# slush_alt_board_rev_c.net
KiCad netlist of a schematic drawn in EAGLE
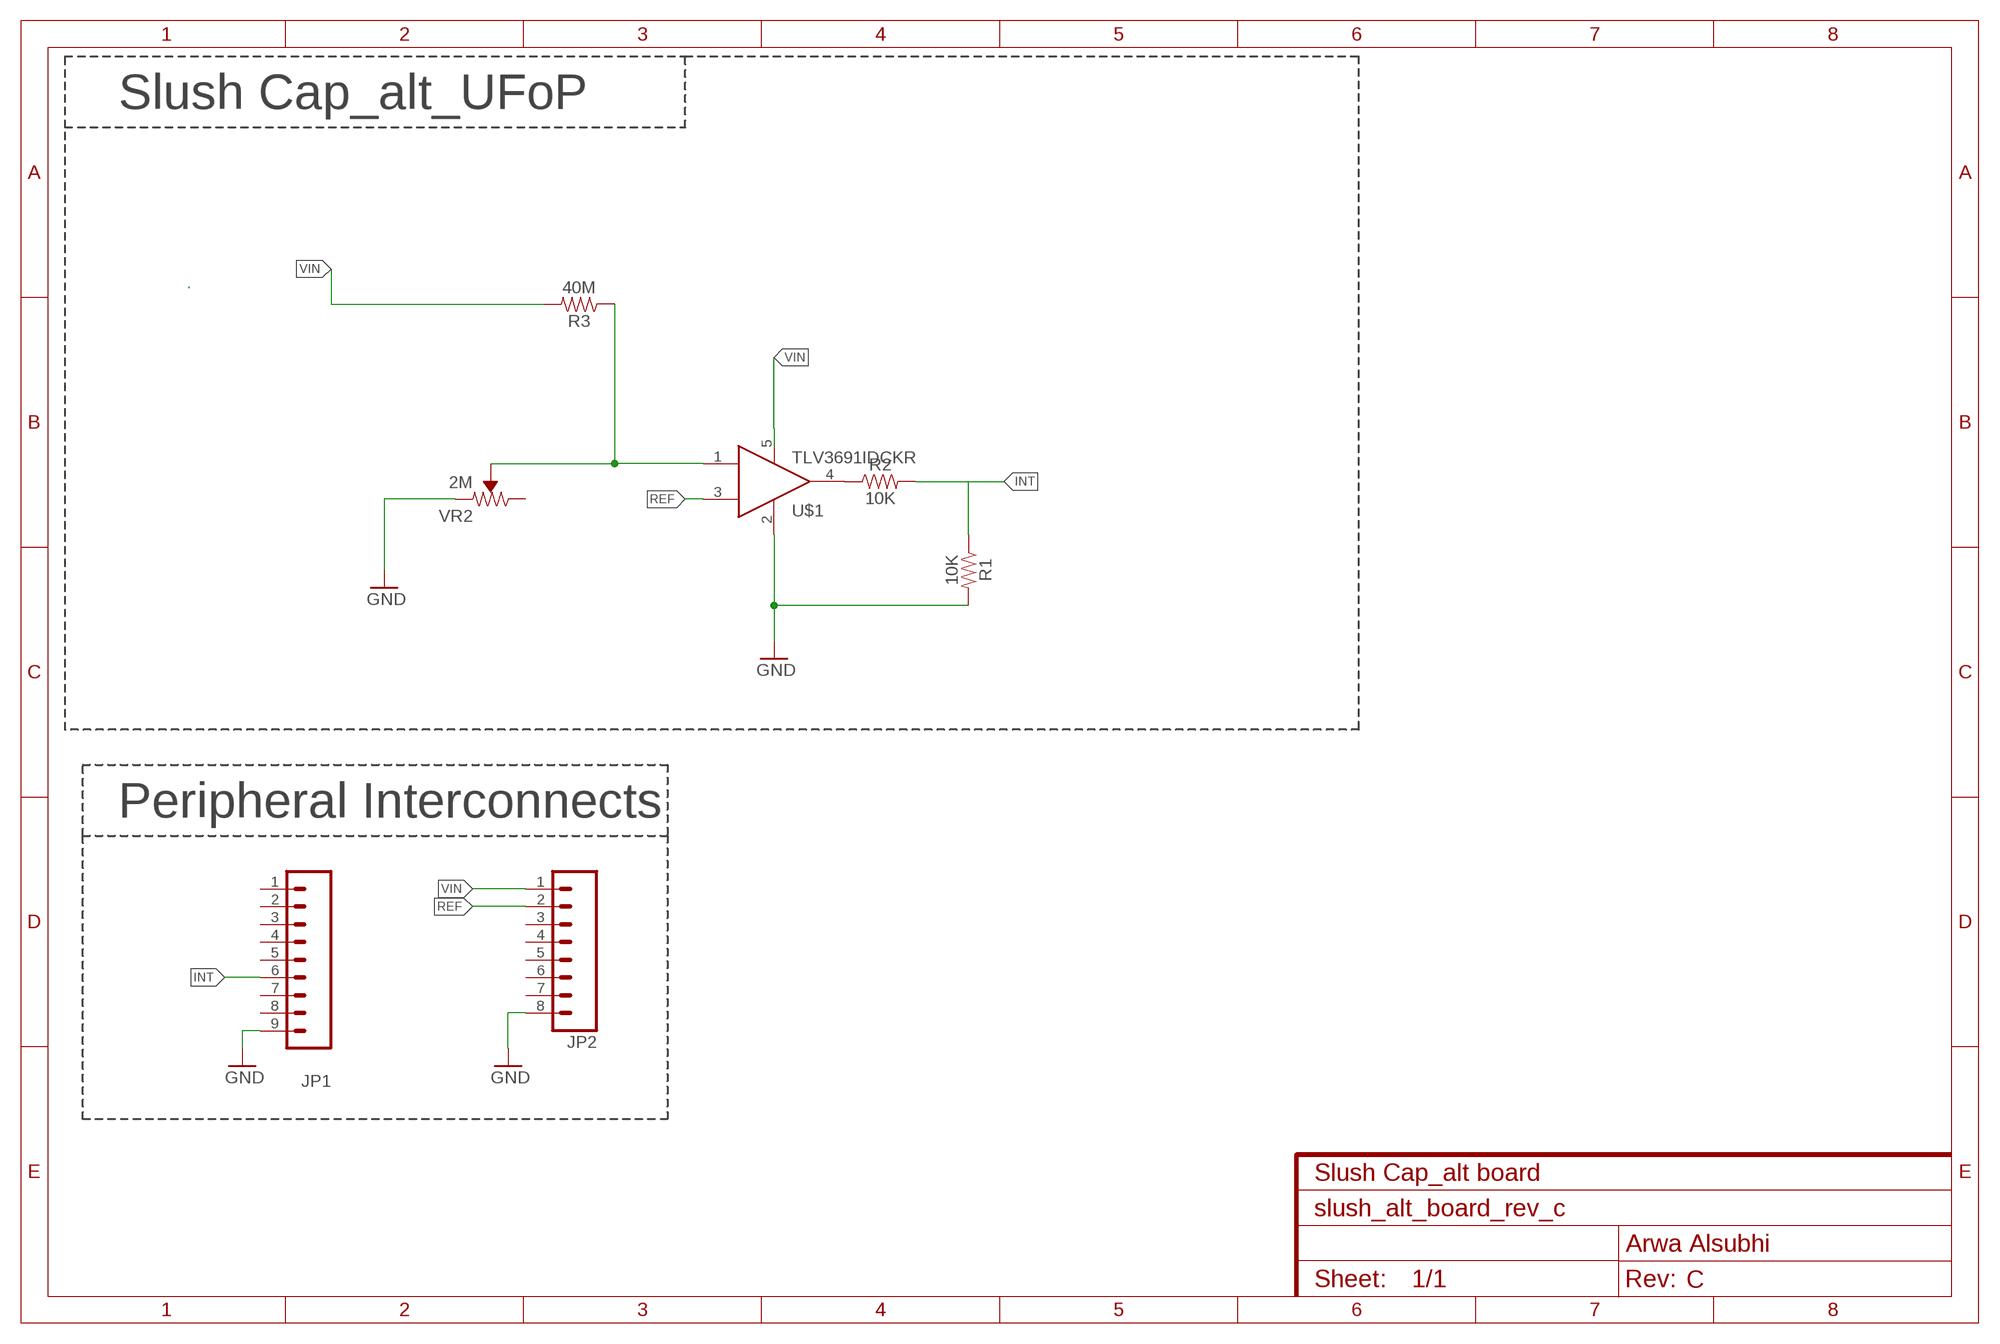
[diagram p0: schematic, sheet 1]

(export (version "E")
  (design (tool "Eeschema 10.0.6"))
  (components
    (comp (ref "JP1")
      (value "M091.27MM")
      (footprint "eagle-import:1X09-1.27MM")
      (fields (field (name "MANUFACTURERPARTNUMBER") "GRPB091VWVN-RC ") (field (name "MPN") "GRPB091VWVN-RC"))
      (libsource (lib "eagle-import") (part "M091.27MM"))
    )
    (comp (ref "JP2")
      (value "M081.27MM")
      (footprint "eagle-import:1X08-1.27MM")
      (fields (field (name "MANUFACTURERPARTNUMBER") "GRPB081VWVN-RC "))
      (libsource (lib "eagle-import") (part "M081.27MM"))
    )
    (comp (ref "R1")
      (value "10K")
      (footprint "eagle-import:0805")
      (libsource (lib "eagle-import") (part "0.3OHM-0805-1/8W-1%"))
    )
    (comp (ref "R2")
      (value "10K")
      (footprint "eagle-import:0805")
      (libsource (lib "eagle-import") (part "0.3OHM-0805-1/8W-1%"))
    )
    (comp (ref "R3")
      (value "40M")
      (footprint "eagle-import:0805")
      (libsource (lib "eagle-import") (part "0.3OHM-0805-1/8W-1%"))
    )
    (comp (ref "U$1")
      (value "TLV3691IDCKR")
      (footprint "eagle-import:SOT353")
      (libsource (lib "eagle-import") (part "TLV3691IDCKR"))
    )
    (comp (ref "VR2")
      (value "2M")
      (footprint "eagle-import:TRIMPOT-SMD-3MM-CLOSED")
      (libsource (lib "eagle-import") (part "TRIMPOT-SMD-3MM-CLOSED-1/8W-20%"))
    )
  )
  (nets
    (net (code "1") (name "GND") (class "Default")
      (node (ref "JP1") (pin "9") (pinfunction "9_9") (pintype "passive"))
      (node (ref "JP2") (pin "8") (pinfunction "8_8") (pintype "passive"))
      (node (ref "R1") (pin "2") (pinfunction "2_2") (pintype "passive"))
      (node (ref "U$1") (pin "2") (pinfunction "2_2") (pintype "bidirectional"))
      (node (ref "VR2") (pin "1") (pinfunction "CCW_1") (pintype "passive"))
    )
    (net (code "2") (name "INT") (class "Default")
      (node (ref "JP1") (pin "6") (pinfunction "6_6") (pintype "passive"))
      (node (ref "R1") (pin "1") (pinfunction "1_1") (pintype "passive"))
      (node (ref "R2") (pin "2") (pinfunction "2_2") (pintype "passive"))
    )
    (net (code "3") (name "Net-(R2-Pad1)") (class "Default")
      (node (ref "R2") (pin "1") (pinfunction "1_1") (pintype "passive"))
      (node (ref "U$1") (pin "4") (pinfunction "4_4") (pintype "bidirectional"))
    )
    (net (code "4") (name "Net-(VR2-WIPER)") (class "Default")
      (node (ref "R3") (pin "1") (pinfunction "1_1") (pintype "passive"))
      (node (ref "U$1") (pin "1") (pinfunction "1_1") (pintype "bidirectional"))
      (node (ref "VR2") (pin "2") (pinfunction "WIPER_2") (pintype "passive"))
    )
    (net (code "5") (name "REF") (class "Default")
      (node (ref "JP2") (pin "2") (pinfunction "2_2") (pintype "passive"))
      (node (ref "U$1") (pin "3") (pinfunction "3_3") (pintype "bidirectional"))
    )
    (net (code "6") (name "VIN") (class "Default")
      (node (ref "JP2") (pin "1") (pinfunction "1_1") (pintype "passive"))
      (node (ref "R3") (pin "2") (pinfunction "2_2") (pintype "passive"))
      (node (ref "U$1") (pin "5") (pinfunction "5_5") (pintype "bidirectional"))
    )
    (net (code "7") (name "unconnected-(JP1-Pad1)") (class "Default")
      (node (ref "JP1") (pin "1") (pinfunction "1_1") (pintype "passive"))
    )
    (net (code "8") (name "unconnected-(JP1-Pad2)") (class "Default")
      (node (ref "JP1") (pin "2") (pinfunction "2_2") (pintype "passive"))
    )
    (net (code "9") (name "unconnected-(JP1-Pad3)") (class "Default")
      (node (ref "JP1") (pin "3") (pinfunction "3_3") (pintype "passive"))
    )
    (net (code "10") (name "unconnected-(JP1-Pad4)") (class "Default")
      (node (ref "JP1") (pin "4") (pinfunction "4_4") (pintype "passive"))
    )
    (net (code "11") (name "unconnected-(JP1-Pad5)") (class "Default")
      (node (ref "JP1") (pin "5") (pinfunction "5_5") (pintype "passive"))
    )
    (net (code "12") (name "unconnected-(JP1-Pad7)") (class "Default")
      (node (ref "JP1") (pin "7") (pinfunction "7_7") (pintype "passive"))
    )
    (net (code "13") (name "unconnected-(JP1-Pad8)") (class "Default")
      (node (ref "JP1") (pin "8") (pinfunction "8_8") (pintype "passive"))
    )
    (net (code "14") (name "unconnected-(JP2-Pad3)") (class "Default")
      (node (ref "JP2") (pin "3") (pinfunction "3_3") (pintype "passive"))
    )
    (net (code "15") (name "unconnected-(JP2-Pad4)") (class "Default")
      (node (ref "JP2") (pin "4") (pinfunction "4_4") (pintype "passive"))
    )
    (net (code "16") (name "unconnected-(JP2-Pad5)") (class "Default")
      (node (ref "JP2") (pin "5") (pinfunction "5_5") (pintype "passive"))
    )
    (net (code "17") (name "unconnected-(JP2-Pad6)") (class "Default")
      (node (ref "JP2") (pin "6") (pinfunction "6_6") (pintype "passive"))
    )
    (net (code "18") (name "unconnected-(JP2-Pad7)") (class "Default")
      (node (ref "JP2") (pin "7") (pinfunction "7_7") (pintype "passive"))
    )
    (net (code "19") (name "unconnected-(VR2-CW-Pad3)") (class "Default")
      (node (ref "VR2") (pin "3") (pinfunction "CW_3") (pintype "passive"))
    )
  )
)
